# VCU_itr2.net
KiCad netlist of a schematic drawn in EAGLE
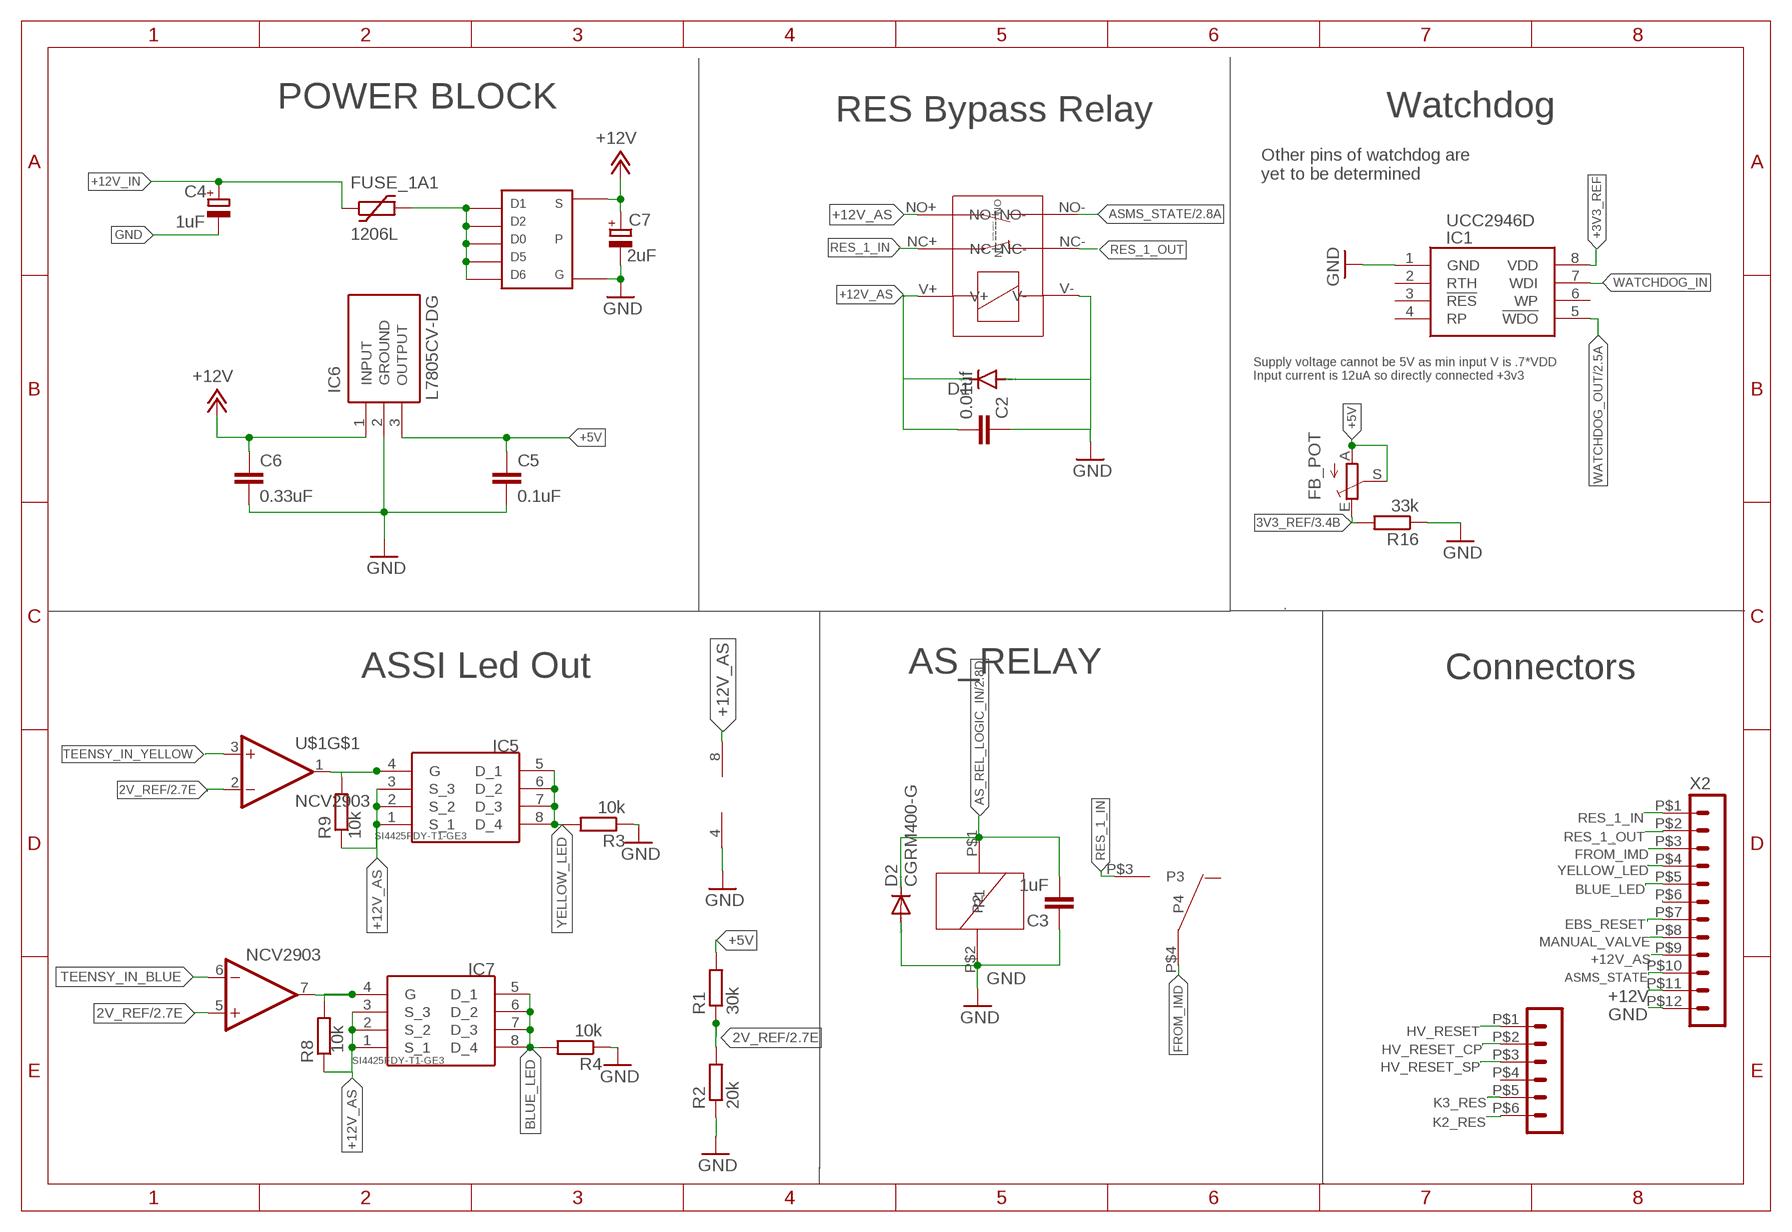
[diagram p0: schematic, sheet 1]
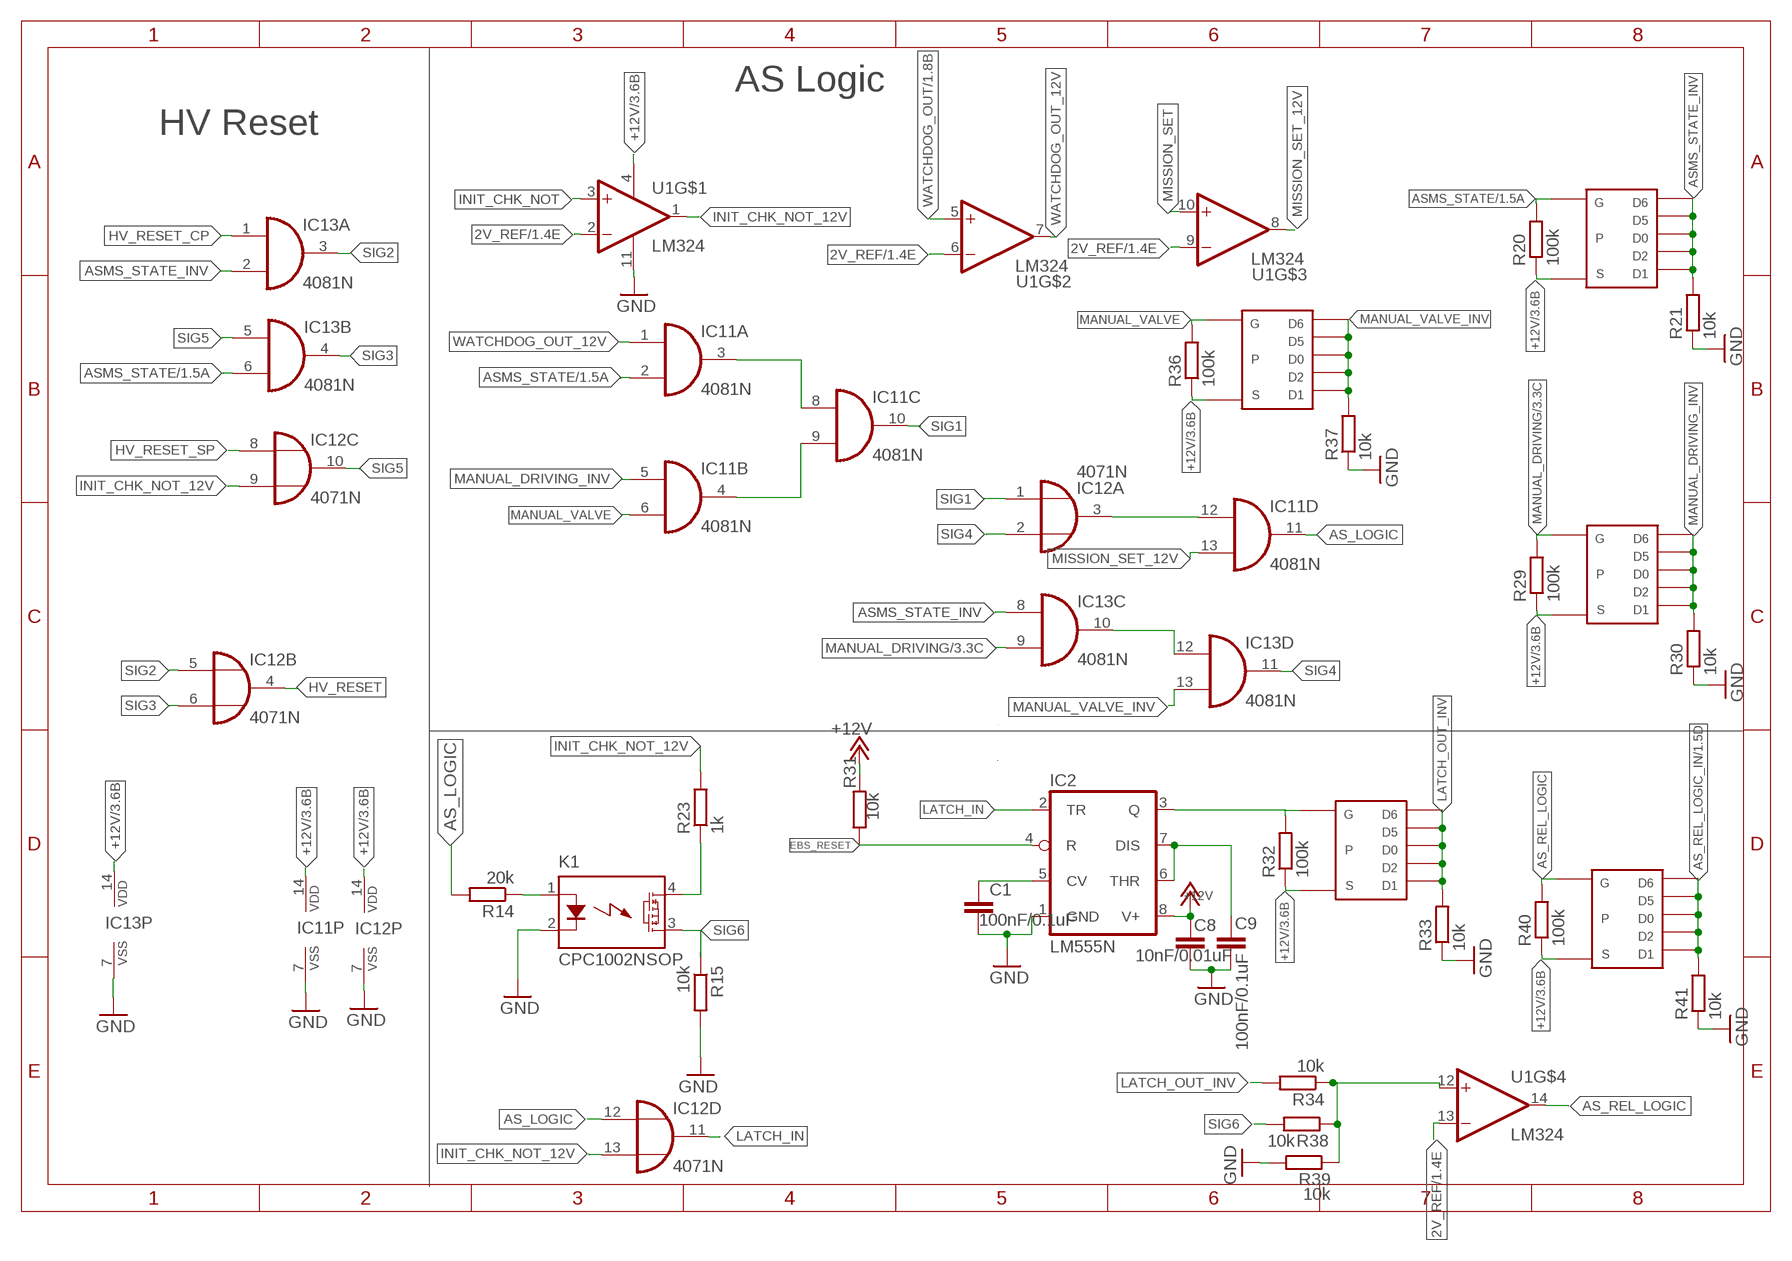
[diagram p1: schematic, sheet 2]
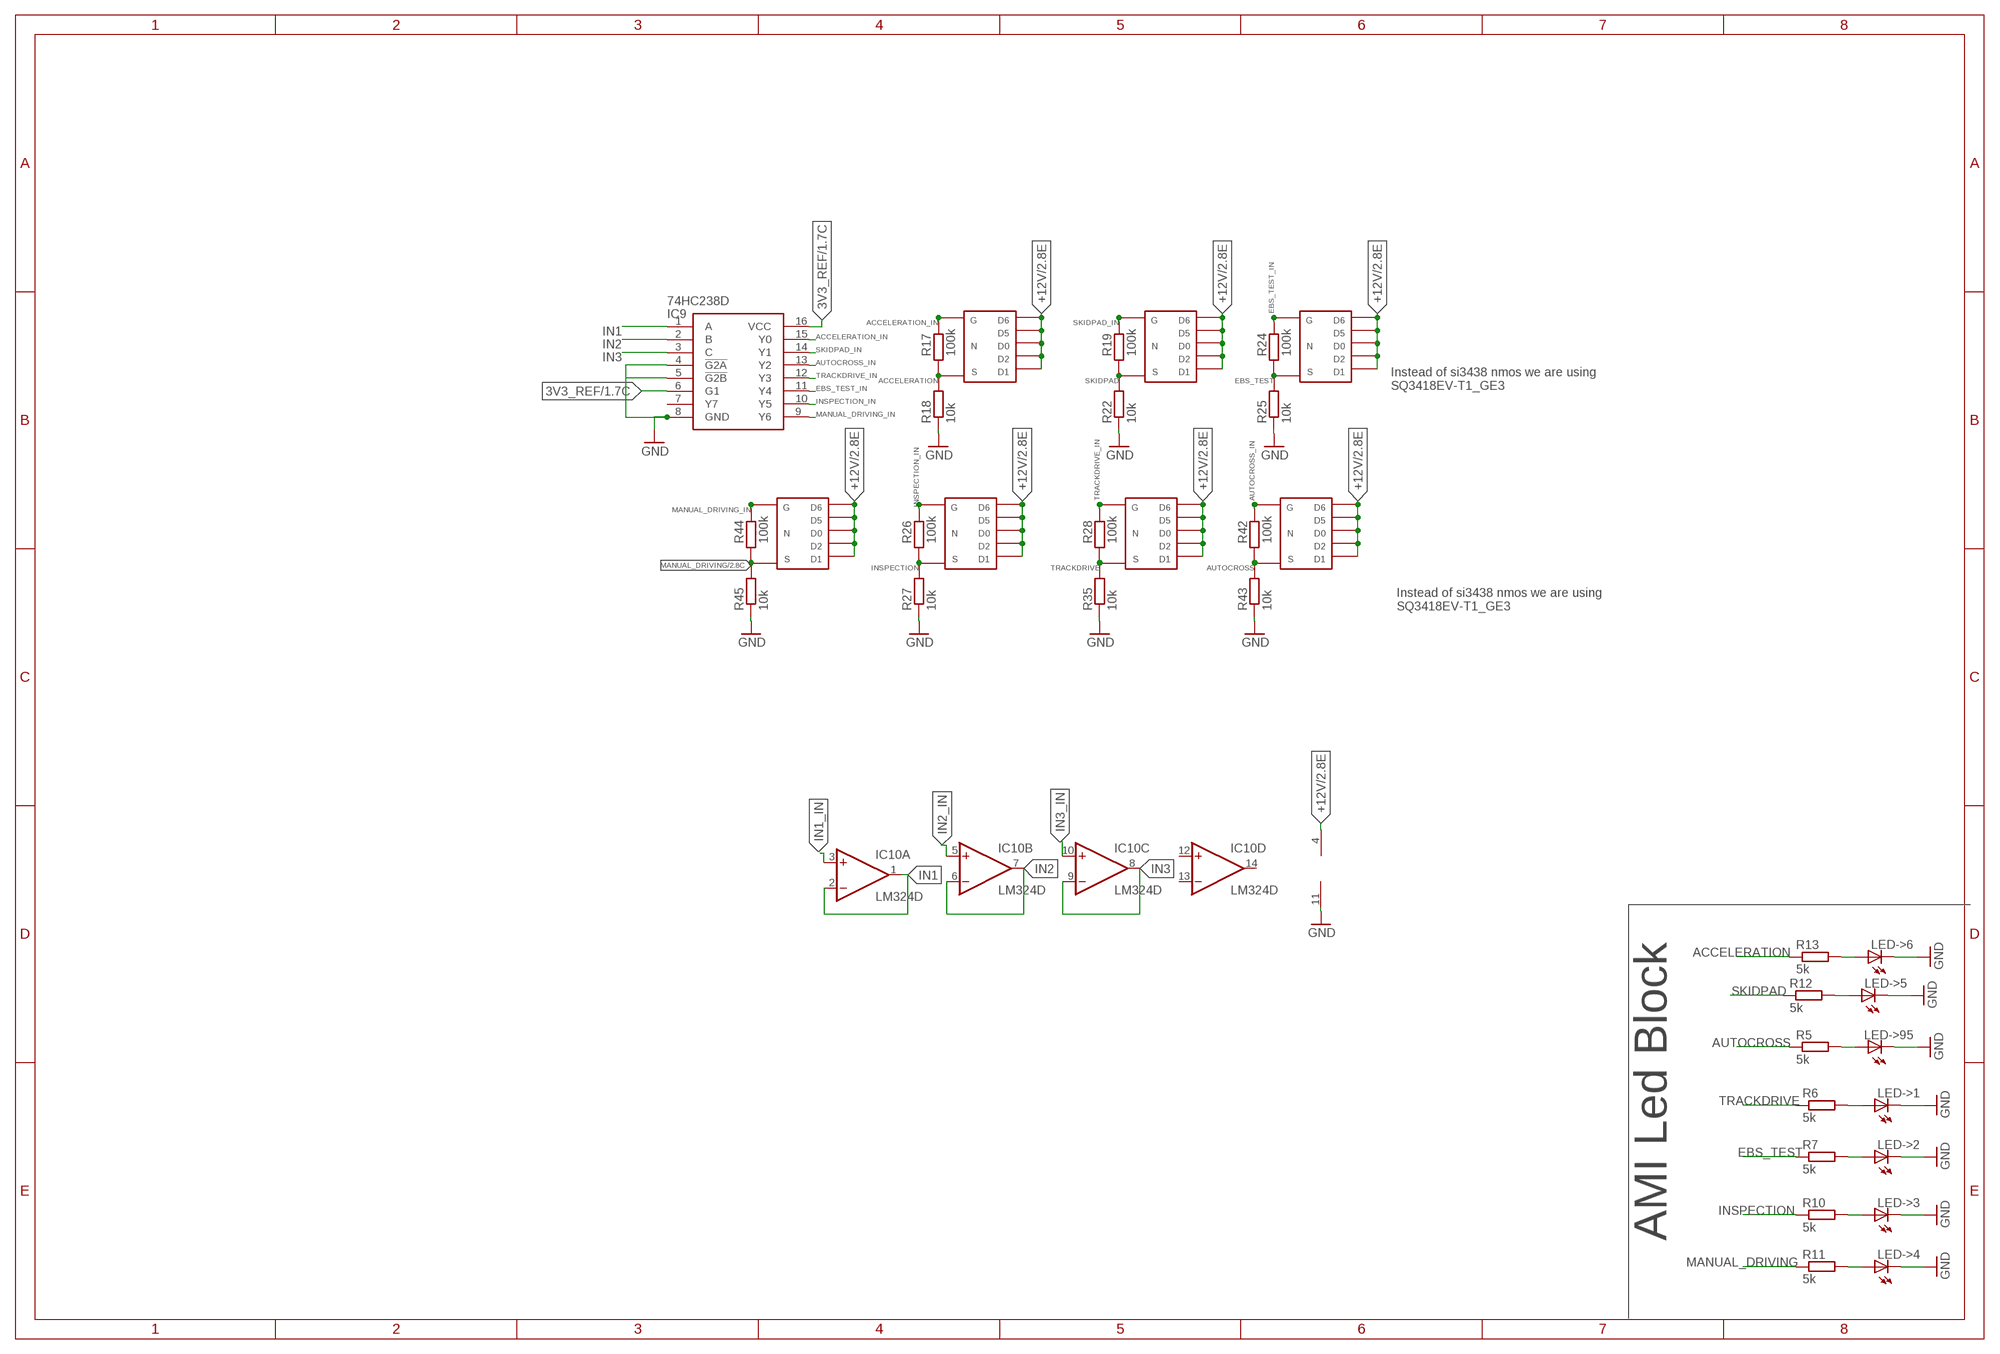
[diagram p2: schematic, sheet 3]

(export (version "E")
  (design (tool "Eeschema 10.0.6"))
  (components
    (comp (ref "BMS-CONN7")
      (value "HEADER_POS6_43045-0612")
      (footprint "eagle-import:43045-0612")
      (libsource (lib "eagle-import") (part "HEADER_POS6_?43045-0612"))
    )
    (comp (ref "C2")
      (value "0.01uf")
      (footprint "eagle-import:C1210")
      (libsource (lib "eagle-import") (part "C-EUC1210"))
    )
    (comp (ref "C3")
      (value "1uF")
      (footprint "eagle-import:C0805")
      (libsource (lib "eagle-import") (part "C-EUC0805"))
    )
    (comp (ref "C4")
      (value "1uF")
      (footprint "eagle-import:SMC_A")
      (libsource (lib "eagle-import") (part "CPOL-EUSMCA"))
    )
    (comp (ref "C5")
      (value "0.1uF")
      (footprint "eagle-import:C0805")
      (libsource (lib "eagle-import") (part "rcl_334_C-EUC0805"))
    )
    (comp (ref "C6")
      (value "0.33uF")
      (footprint "eagle-import:C0805")
      (libsource (lib "eagle-import") (part "rcl_334_C-EUC0805"))
    )
    (comp (ref "C7")
      (value "2uF")
      (footprint "eagle-import:E2,5-6")
      (libsource (lib "eagle-import") (part "CPOL-EUE2.5-6"))
    )
    (comp (ref "D1")
      (value "DIODE-DO214AC")
      (footprint "eagle-import:DO214AC")
      (libsource (lib "eagle-import") (part "DIODE-DO214AC"))
    )
    (comp (ref "D2")
      (value "CGRM400-G")
      (footprint "eagle-import:SOD-123_MINI-SMA")
      (libsource (lib "eagle-import") (part "CGRM400-G"))
    )
    (comp (ref "FB_POT")
      (value "17k")
      (footprint "eagle-import:S63S")
      (libsource (lib "eagle-import") (part "TRIM_EU-S63S"))
    )
    (comp (ref "FUSE_1A1")
      (value "1206L")
      (footprint "eagle-import:1206L")
      (libsource (lib "eagle-import") (part "1206L"))
    )
    (comp (ref "IC1")
      (value "UCC2946D")
      (footprint "eagle-import:SOIC127P600X175-8N")
      (fields (field (name "MOUSER_PART_NUMBER") "595-UCC2946D"))
      (libsource (lib "eagle-import") (part "UCC2946D"))
    )
    (comp (ref "IC5")
      (value "SI4425FDY-T1-GE3")
      (footprint "eagle-import:SOIC127P600X175-8N")
      (fields (field (name "MOUSER_PART_NUMBER") "78-SI4425FDY-T1-GE3"))
      (libsource (lib "eagle-import") (part "SI4425FDY-T1-GE3"))
    )
    (comp (ref "IC6")
      (value "L7805CV-DG")
      (footprint "eagle-import:TO255P460X1020X2008-3P")
      (fields (field (name "MOUSER_PART_NUMBER") "511-L7805CV-DG"))
      (libsource (lib "eagle-import") (part "L7805CV-DG"))
    )
    (comp (ref "IC7")
      (value "SI4425FDY-T1-GE3")
      (footprint "eagle-import:SOIC127P600X175-8N")
      (fields (field (name "MOUSER_PART_NUMBER") "78-SI4425FDY-T1-GE3"))
      (libsource (lib "eagle-import") (part "SI4425FDY-T1-GE3"))
    )
    (comp (ref "R1")
      (value "30k")
      (footprint "eagle-import:M0805")
      (libsource (lib "eagle-import") (part "IIT_BOMBAY_Racing2_R-EU_M0805"))
    )
    (comp (ref "R2")
      (value "20k")
      (footprint "eagle-import:M0805")
      (libsource (lib "eagle-import") (part "IIT_BOMBAY_Racing2_R-EU_M0805"))
    )
    (comp (ref "R3")
      (value "10k")
      (footprint "eagle-import:M0805")
      (libsource (lib "eagle-import") (part "IIT_BOMBAY_Racing2_R-EU_M0805"))
    )
    (comp (ref "R4")
      (value "10k")
      (footprint "eagle-import:M0805")
      (libsource (lib "eagle-import") (part "IIT_BOMBAY_Racing2_R-EU_M0805"))
    )
    (comp (ref "R8")
      (value "10k")
      (footprint "eagle-import:M0805")
      (libsource (lib "eagle-import") (part "IIT_BOMBAY_Racing2_R-EU_M0805"))
    )
    (comp (ref "R9")
      (value "10k")
      (footprint "eagle-import:M0805")
      (libsource (lib "eagle-import") (part "IIT_BOMBAY_Racing2_R-EU_M0805"))
    )
    (comp (ref "R16")
      (value "33k")
      (footprint "eagle-import:M0805")
      (libsource (lib "eagle-import") (part "IIT_BOMBAY_Racing2_R-EU_M0805"))
    )
    (comp (ref "SI1")
      (value "TSOP-6_PMOS")
      (footprint "eagle-import:TSOP-6_PMOS")
      (libsource (lib "eagle-import") (part "TSOP-6_PMOS"))
    )
    (comp (ref "U$1")
      (value "NCV2903")
      (footprint "eagle-import:SOIC-8")
      (libsource (lib "eagle-import") (part "NCV2903"))
    )
    (comp (ref "U$2")
      (value "G6DN_RELAY")
      (footprint "eagle-import:G6DN_RELAY")
      (libsource (lib "eagle-import") (part "G6DN_RELAY"))
    )
    (comp (ref "U$9")
      (value "SFM_RELAY")
      (footprint "eagle-import:SFM_RELAY")
      (libsource (lib "eagle-import") (part "SFM_RELAY"))
    )
    (comp (ref "X2")
      (value "HEADER_POS12_44914-1201")
      (footprint "eagle-import:44914-1201")
      (libsource (lib "eagle-import") (part "HEADER_POS12_?44914-1201"))
    )
    (comp (ref "IC9")
      (value "74HC238D")
      (footprint "eagle-import:SOIC127P600X175-16N")
      (fields (field (name "MOUSER_PART_NUMBER") "757-74HC238D"))
      (libsource (lib "eagle-import") (part "74HC238D"))
    )
    (comp (ref "IC10")
      (value "LM324D")
      (footprint "eagle-import:SO14")
      (libsource (lib "eagle-import") (part "LM324D"))
    )
    (comp (ref "LED->1")
      (value "LED-FKIT-1206")
      (footprint "eagle-import:FKIT-LED-1206")
      (libsource (lib "eagle-import") (part "LED-FKIT-1206"))
    )
    (comp (ref "LED->2")
      (value "LED-FKIT-1206")
      (footprint "eagle-import:FKIT-LED-1206")
      (libsource (lib "eagle-import") (part "LED-FKIT-1206"))
    )
    (comp (ref "LED->3")
      (value "LED-FKIT-1206")
      (footprint "eagle-import:FKIT-LED-1206")
      (libsource (lib "eagle-import") (part "LED-FKIT-1206"))
    )
    (comp (ref "LED->4")
      (value "LED-FKIT-1206")
      (footprint "eagle-import:FKIT-LED-1206")
      (libsource (lib "eagle-import") (part "LED-FKIT-1206"))
    )
    (comp (ref "LED->5")
      (value "LED-FKIT-1206")
      (footprint "eagle-import:FKIT-LED-1206")
      (libsource (lib "eagle-import") (part "LED-FKIT-1206"))
    )
    (comp (ref "LED->6")
      (value "LED-FKIT-1206")
      (footprint "eagle-import:FKIT-LED-1206")
      (libsource (lib "eagle-import") (part "LED-FKIT-1206"))
    )
    (comp (ref "LED->95")
      (value "LED-FKIT-1206")
      (footprint "eagle-import:FKIT-LED-1206")
      (libsource (lib "eagle-import") (part "LED-FKIT-1206"))
    )
    (comp (ref "R5")
      (value "5k")
      (footprint "eagle-import:R0805")
      (libsource (lib "eagle-import") (part "R-EU_R0805"))
    )
    (comp (ref "R6")
      (value "5k")
      (footprint "eagle-import:R0805")
      (libsource (lib "eagle-import") (part "R-EU_R0805"))
    )
    (comp (ref "R7")
      (value "5k")
      (footprint "eagle-import:R0805")
      (libsource (lib "eagle-import") (part "R-EU_R0805"))
    )
    (comp (ref "R10")
      (value "5k")
      (footprint "eagle-import:R0805")
      (libsource (lib "eagle-import") (part "R-EU_R0805"))
    )
    (comp (ref "R11")
      (value "5k")
      (footprint "eagle-import:R0805")
      (libsource (lib "eagle-import") (part "R-EU_R0805"))
    )
    (comp (ref "R12")
      (value "5k")
      (footprint "eagle-import:R0805")
      (libsource (lib "eagle-import") (part "R-EU_R0805"))
    )
    (comp (ref "R13")
      (value "5k")
      (footprint "eagle-import:R0805")
      (libsource (lib "eagle-import") (part "R-EU_R0805"))
    )
    (comp (ref "R17")
      (value "100k")
      (footprint "eagle-import:R0805")
      (libsource (lib "eagle-import") (part "R-EU_R0805"))
    )
    (comp (ref "R18")
      (value "10k")
      (footprint "eagle-import:M0805")
      (libsource (lib "eagle-import") (part "IIT_BOMBAY_Racing2_R-EU_M0805"))
    )
    (comp (ref "R19")
      (value "100k")
      (footprint "eagle-import:R0805")
      (libsource (lib "eagle-import") (part "R-EU_R0805"))
    )
    (comp (ref "R22")
      (value "10k")
      (footprint "eagle-import:M0805")
      (libsource (lib "eagle-import") (part "IIT_BOMBAY_Racing2_R-EU_M0805"))
    )
    (comp (ref "R24")
      (value "100k")
      (footprint "eagle-import:R0805")
      (libsource (lib "eagle-import") (part "R-EU_R0805"))
    )
    (comp (ref "R25")
      (value "10k")
      (footprint "eagle-import:M0805")
      (libsource (lib "eagle-import") (part "IIT_BOMBAY_Racing2_R-EU_M0805"))
    )
    (comp (ref "R26")
      (value "100k")
      (footprint "eagle-import:R0805")
      (libsource (lib "eagle-import") (part "R-EU_R0805"))
    )
    (comp (ref "R27")
      (value "10k")
      (footprint "eagle-import:M0805")
      (libsource (lib "eagle-import") (part "IIT_BOMBAY_Racing2_R-EU_M0805"))
    )
    (comp (ref "R28")
      (value "100k")
      (footprint "eagle-import:R0805")
      (libsource (lib "eagle-import") (part "R-EU_R0805"))
    )
    (comp (ref "R35")
      (value "10k")
      (footprint "eagle-import:M0805")
      (libsource (lib "eagle-import") (part "IIT_BOMBAY_Racing2_R-EU_M0805"))
    )
    (comp (ref "R42")
      (value "100k")
      (footprint "eagle-import:R0805")
      (libsource (lib "eagle-import") (part "R-EU_R0805"))
    )
    (comp (ref "R43")
      (value "10k")
      (footprint "eagle-import:M0805")
      (libsource (lib "eagle-import") (part "IIT_BOMBAY_Racing2_R-EU_M0805"))
    )
    (comp (ref "R44")
      (value "100k")
      (footprint "eagle-import:R0805")
      (libsource (lib "eagle-import") (part "R-EU_R0805"))
    )
    (comp (ref "R45")
      (value "10k")
      (footprint "eagle-import:M0805")
      (libsource (lib "eagle-import") (part "IIT_BOMBAY_Racing2_R-EU_M0805"))
    )
    (comp (ref "U$13")
      (value "TSOP-6_NMOS")
      (footprint "eagle-import:TSOP-6_NMOS")
      (libsource (lib "eagle-import") (part "TSOP-6_NMOS"))
    )
    (comp (ref "U$14")
      (value "TSOP-6_NMOS")
      (footprint "eagle-import:TSOP-6_NMOS")
      (libsource (lib "eagle-import") (part "TSOP-6_NMOS"))
    )
    (comp (ref "U$15")
      (value "TSOP-6_NMOS")
      (footprint "eagle-import:TSOP-6_NMOS")
      (libsource (lib "eagle-import") (part "TSOP-6_NMOS"))
    )
    (comp (ref "U$16")
      (value "TSOP-6_NMOS")
      (footprint "eagle-import:TSOP-6_NMOS")
      (libsource (lib "eagle-import") (part "TSOP-6_NMOS"))
    )
    (comp (ref "U$17")
      (value "TSOP-6_NMOS")
      (footprint "eagle-import:TSOP-6_NMOS")
      (libsource (lib "eagle-import") (part "TSOP-6_NMOS"))
    )
    (comp (ref "U$18")
      (value "TSOP-6_NMOS")
      (footprint "eagle-import:TSOP-6_NMOS")
      (libsource (lib "eagle-import") (part "TSOP-6_NMOS"))
    )
    (comp (ref "U$19")
      (value "TSOP-6_NMOS")
      (footprint "eagle-import:TSOP-6_NMOS")
      (libsource (lib "eagle-import") (part "TSOP-6_NMOS"))
    )
    (comp (ref "C1")
      (value "100nF/0.1uF")
      (footprint "eagle-import:C0805")
      (libsource (lib "eagle-import") (part "C-EUC0805"))
    )
    (comp (ref "C8")
      (value "10nF/0.01uF")
      (footprint "eagle-import:C0805")
      (libsource (lib "eagle-import") (part "C-EUC0805"))
    )
    (comp (ref "C9")
      (value "100nF/0.1uF")
      (footprint "eagle-import:C0805")
      (libsource (lib "eagle-import") (part "C-EUC0805"))
    )
    (comp (ref "IC2")
      (value "LM555N")
      (footprint "eagle-import:DIL08")
      (libsource (lib "eagle-import") (part "555NLM"))
    )
    (comp (ref "IC11")
      (value "4081N")
      (footprint "eagle-import:DIL14")
      (libsource (lib "eagle-import") (part "4081N"))
    )
    (comp (ref "IC12")
      (value "4071N")
      (footprint "eagle-import:DIL14")
      (libsource (lib "eagle-import") (part "4071N"))
    )
    (comp (ref "IC13")
      (value "4081N")
      (footprint "eagle-import:DIL14")
      (libsource (lib "eagle-import") (part "4081N"))
    )
    (comp (ref "K1")
      (value "CPC1002NSOP")
      (footprint "eagle-import:SOP04")
      (libsource (lib "eagle-import") (part "CPC1002NSOP"))
    )
    (comp (ref "R14")
      (value "20k")
      (footprint "eagle-import:R0805")
      (libsource (lib "eagle-import") (part "R-EU_R0805"))
    )
    (comp (ref "R15")
      (value "10k")
      (footprint "eagle-import:R0805")
      (libsource (lib "eagle-import") (part "R-EU_R0805"))
    )
    (comp (ref "R20")
      (value "100k")
      (footprint "eagle-import:M0805")
      (libsource (lib "eagle-import") (part "IIT_BOMBAY_Racing2_R-EU_M0805"))
    )
    (comp (ref "R21")
      (value "10k")
      (footprint "eagle-import:M0805")
      (libsource (lib "eagle-import") (part "IIT_BOMBAY_Racing2_R-EU_M0805"))
    )
    (comp (ref "R23")
      (value "1k")
      (footprint "eagle-import:M0805")
      (libsource (lib "eagle-import") (part "R-EU_M0805"))
    )
    (comp (ref "R29")
      (value "100k")
      (footprint "eagle-import:M0805")
      (libsource (lib "eagle-import") (part "IIT_BOMBAY_Racing2_R-EU_M0805"))
    )
    (comp (ref "R30")
      (value "10k")
      (footprint "eagle-import:M0805")
      (libsource (lib "eagle-import") (part "IIT_BOMBAY_Racing2_R-EU_M0805"))
    )
    (comp (ref "R31")
      (value "10k")
      (footprint "eagle-import:R0805")
      (libsource (lib "eagle-import") (part "R-EU_R0805"))
    )
    (comp (ref "R32")
      (value "100k")
      (footprint "eagle-import:M0805")
      (libsource (lib "eagle-import") (part "IIT_BOMBAY_Racing2_R-EU_M0805"))
    )
    (comp (ref "R33")
      (value "10k")
      (footprint "eagle-import:M0805")
      (libsource (lib "eagle-import") (part "IIT_BOMBAY_Racing2_R-EU_M0805"))
    )
    (comp (ref "R34")
      (value "10k")
      (footprint "eagle-import:M0805")
      (libsource (lib "eagle-import") (part "IIT_BOMBAY_Racing2_R-EU_M0805"))
    )
    (comp (ref "R36")
      (value "100k")
      (footprint "eagle-import:M0805")
      (libsource (lib "eagle-import") (part "IIT_BOMBAY_Racing2_R-EU_M0805"))
    )
    (comp (ref "R37")
      (value "10k")
      (footprint "eagle-import:M0805")
      (libsource (lib "eagle-import") (part "IIT_BOMBAY_Racing2_R-EU_M0805"))
    )
    (comp (ref "R38")
      (value "10k")
      (footprint "eagle-import:M0805")
      (libsource (lib "eagle-import") (part "IIT_BOMBAY_Racing2_R-EU_M0805"))
    )
    (comp (ref "R39")
      (value "10k")
      (footprint "eagle-import:M0805")
      (libsource (lib "eagle-import") (part "IIT_BOMBAY_Racing2_R-EU_M0805"))
    )
    (comp (ref "R40")
      (value "100k")
      (footprint "eagle-import:M0805")
      (libsource (lib "eagle-import") (part "IIT_BOMBAY_Racing2_R-EU_M0805"))
    )
    (comp (ref "R41")
      (value "10k")
      (footprint "eagle-import:M0805")
      (libsource (lib "eagle-import") (part "IIT_BOMBAY_Racing2_R-EU_M0805"))
    )
    (comp (ref "SI2")
      (value "TSOP-6_PMOS")
      (footprint "eagle-import:TSOP-6_PMOS")
      (libsource (lib "eagle-import") (part "TSOP-6_PMOS"))
    )
    (comp (ref "SI3")
      (value "TSOP-6_PMOS")
      (footprint "eagle-import:TSOP-6_PMOS")
      (libsource (lib "eagle-import") (part "TSOP-6_PMOS"))
    )
    (comp (ref "SI5")
      (value "TSOP-6_PMOS")
      (footprint "eagle-import:TSOP-6_PMOS")
      (libsource (lib "eagle-import") (part "TSOP-6_PMOS"))
    )
    (comp (ref "SI6")
      (value "TSOP-6_PMOS")
      (footprint "eagle-import:TSOP-6_PMOS")
      (libsource (lib "eagle-import") (part "TSOP-6_PMOS"))
    )
    (comp (ref "SI7")
      (value "TSOP-6_PMOS")
      (footprint "eagle-import:TSOP-6_PMOS")
      (libsource (lib "eagle-import") (part "TSOP-6_PMOS"))
    )
    (comp (ref "U1")
      (value "LM324")
      (footprint "eagle-import:SOIC127P600X175-14N")
      (description "Quad OpAmp")
      (fields (field (name "MF") "Intersil") (field (name "MP") "LM324.."))
      (libsource (lib "eagle-import") (part "LM324"))
    )
  )
  (nets
    (net (code "1") (name "+3V3_REF") (class "Default")
      (node (ref "IC1") (pin "8") (pinfunction "VDD_8") (pintype "bidirectional"))
    )
    (net (code "2") (name "+5V") (class "Default")
      (node (ref "C5") (pin "1") (pinfunction "1_1") (pintype "passive"))
      (node (ref "FB_POT") (pin "A") (pinfunction "A_A") (pintype "passive"))
      (node (ref "FB_POT") (pin "S") (pinfunction "S_S") (pintype "passive"))
      (node (ref "IC6") (pin "3") (pinfunction "OUTPUT_3") (pintype "bidirectional"))
      (node (ref "R1") (pin "2") (pinfunction "2_2") (pintype "passive"))
    )
    (net (code "3") (name "+12V") (class "Default")
      (node (ref "C6") (pin "1") (pinfunction "1_1") (pintype "passive"))
      (node (ref "C7") (pin "+") (pinfunction "+_+") (pintype "passive"))
      (node (ref "C8") (pin "1") (pinfunction "1_1") (pintype "passive"))
      (node (ref "IC11") (pin "14") (pinfunction "VDD_14") (pintype "power_in"))
      (node (ref "IC12") (pin "14") (pinfunction "VDD_14") (pintype "power_in"))
      (node (ref "IC13") (pin "14") (pinfunction "VDD_14") (pintype "power_in"))
      (node (ref "IC2") (pin "8") (pinfunction "V+_8") (pintype "power_in"))
      (node (ref "IC6") (pin "1") (pinfunction "INPUT_1") (pintype "bidirectional"))
      (node (ref "R20") (pin "1") (pinfunction "1_1") (pintype "passive"))
      (node (ref "R29") (pin "1") (pinfunction "1_1") (pintype "passive"))
      (node (ref "R31") (pin "2") (pinfunction "2_2") (pintype "passive"))
      (node (ref "R32") (pin "1") (pinfunction "1_1") (pintype "passive"))
      (node (ref "R36") (pin "1") (pinfunction "1_1") (pintype "passive"))
      (node (ref "R40") (pin "1") (pinfunction "1_1") (pintype "passive"))
      (node (ref "SI1") (pin "S") (pinfunction "S_S") (pintype "bidirectional"))
      (node (ref "SI2") (pin "S") (pinfunction "S_S") (pintype "bidirectional"))
      (node (ref "SI3") (pin "S") (pinfunction "S_S") (pintype "bidirectional"))
      (node (ref "SI5") (pin "S") (pinfunction "S_S") (pintype "bidirectional"))
      (node (ref "SI6") (pin "S") (pinfunction "S_S") (pintype "bidirectional"))
      (node (ref "SI7") (pin "S") (pinfunction "S_S") (pintype "bidirectional"))
      (node (ref "U$13") (pin "1") (pinfunction "1_1") (pintype "bidirectional"))
      (node (ref "U$13") (pin "2") (pinfunction "2_2") (pintype "bidirectional"))
      (node (ref "U$13") (pin "5") (pinfunction "5_5") (pintype "bidirectional"))
      (node (ref "U$13") (pin "6") (pinfunction "6_6") (pintype "bidirectional"))
      (node (ref "U$13") (pin "D") (pinfunction "D0_D") (pintype "bidirectional"))
      (node (ref "U$14") (pin "1") (pinfunction "1_1") (pintype "bidirectional"))
      (node (ref "U$14") (pin "2") (pinfunction "2_2") (pintype "bidirectional"))
      (node (ref "U$14") (pin "5") (pinfunction "5_5") (pintype "bidirectional"))
      (node (ref "U$14") (pin "6") (pinfunction "6_6") (pintype "bidirectional"))
      (node (ref "U$14") (pin "D") (pinfunction "D0_D") (pintype "bidirectional"))
      (node (ref "U$15") (pin "1") (pinfunction "1_1") (pintype "bidirectional"))
      (node (ref "U$15") (pin "2") (pinfunction "2_2") (pintype "bidirectional"))
      (node (ref "U$15") (pin "5") (pinfunction "5_5") (pintype "bidirectional"))
      (node (ref "U$15") (pin "6") (pinfunction "6_6") (pintype "bidirectional"))
      (node (ref "U$15") (pin "D") (pinfunction "D0_D") (pintype "bidirectional"))
      (node (ref "U$16") (pin "1") (pinfunction "1_1") (pintype "bidirectional"))
      (node (ref "U$16") (pin "2") (pinfunction "2_2") (pintype "bidirectional"))
      (node (ref "U$16") (pin "5") (pinfunction "5_5") (pintype "bidirectional"))
      (node (ref "U$16") (pin "6") (pinfunction "6_6") (pintype "bidirectional"))
      (node (ref "U$16") (pin "D") (pinfunction "D0_D") (pintype "bidirectional"))
      (node (ref "U$17") (pin "1") (pinfunction "1_1") (pintype "bidirectional"))
      (node (ref "U$17") (pin "2") (pinfunction "2_2") (pintype "bidirectional"))
      (node (ref "U$17") (pin "5") (pinfunction "5_5") (pintype "bidirectional"))
      (node (ref "U$17") (pin "6") (pinfunction "6_6") (pintype "bidirectional"))
      (node (ref "U$17") (pin "D") (pinfunction "D0_D") (pintype "bidirectional"))
      (node (ref "U$18") (pin "1") (pinfunction "1_1") (pintype "bidirectional"))
      (node (ref "U$18") (pin "2") (pinfunction "2_2") (pintype "bidirectional"))
      (node (ref "U$18") (pin "5") (pinfunction "5_5") (pintype "bidirectional"))
      (node (ref "U$18") (pin "6") (pinfunction "6_6") (pintype "bidirectional"))
      (node (ref "U$18") (pin "D") (pinfunction "D0_D") (pintype "bidirectional"))
      (node (ref "U$19") (pin "1") (pinfunction "1_1") (pintype "bidirectional"))
      (node (ref "U$19") (pin "2") (pinfunction "2_2") (pintype "bidirectional"))
      (node (ref "U$19") (pin "5") (pinfunction "5_5") (pintype "bidirectional"))
      (node (ref "U$19") (pin "6") (pinfunction "6_6") (pintype "bidirectional"))
      (node (ref "U$19") (pin "D") (pinfunction "D0_D") (pintype "bidirectional"))
      (node (ref "U1") (pin "4") (pinfunction "VCC+_4") (pintype "power_in"))
      (node (ref "X2") (pin "P$11") (pinfunction "11_P$11") (pintype "passive"))
    )
    (net (code "4") (name "+12V_AS") (class "Default")
      (node (ref "C2") (pin "2") (pinfunction "2_2") (pintype "passive"))
      (node (ref "D1") (pin "C") (pinfunction "C_C") (pintype "passive"))
      (node (ref "IC5") (pin "1") (pinfunction "S_1_1") (pintype "bidirectional"))
      (node (ref "IC5") (pin "2") (pinfunction "S_2_2") (pintype "bidirectional"))
      (node (ref "IC5") (pin "3") (pinfunction "S_3_3") (pintype "bidirectional"))
      (node (ref "IC7") (pin "1") (pinfunction "S_1_1") (pintype "bidirectional"))
      (node (ref "IC7") (pin "2") (pinfunction "S_2_2") (pintype "bidirectional"))
      (node (ref "IC7") (pin "3") (pinfunction "S_3_3") (pintype "bidirectional"))
      (node (ref "R8") (pin "1") (pinfunction "1_1") (pintype "passive"))
      (node (ref "R9") (pin "1") (pinfunction "1_1") (pintype "passive"))
      (node (ref "U$1") (pin "8") (pinfunction "V+_8") (pintype "power_in"))
      (node (ref "U$9") (pin "NO+") (pinfunction "NO+_NO+") (pintype "bidirectional"))
      (node (ref "U$9") (pin "V+") (pinfunction "V+_V+") (pintype "bidirectional"))
      (node (ref "X2") (pin "P$9") (pinfunction "9_P$9") (pintype "passive"))
    )
    (net (code "5") (name "+12V_IN") (class "Default")
      (node (ref "C4") (pin "+") (pinfunction "+_+") (pintype "passive"))
      (node (ref "FUSE_1A1") (pin "P$1") (pinfunction "1_P$1") (pintype "passive"))
    )
    (net (code "6") (name "2V_REF") (class "Default")
      (node (ref "R1") (pin "1") (pinfunction "1_1") (pintype "passive"))
      (node (ref "R2") (pin "2") (pinfunction "2_2") (pintype "passive"))
      (node (ref "U$1") (pin "2") (pinfunction "-IN_2") (pintype "input"))
      (node (ref "U$1") (pin "5") (pinfunction "+IN_5") (pintype "input"))
      (node (ref "U1") (pin "13") (pinfunction "INVERTING_INPUT4_13") (pintype "input"))
      (node (ref "U1") (pin "2") (pinfunction "INVERTING_INPUT1_2") (pintype "input"))
      (node (ref "U1") (pin "6") (pinfunction "INVERTING_INPUT2_6") (pintype "input"))
      (node (ref "U1") (pin "9") (pinfunction "INVERTING_INPUT3_9") (pintype "input"))
    )
    (net (code "7") (name "3V3_REF") (class "Default")
      (node (ref "FB_POT") (pin "E") (pinfunction "E_E") (pintype "passive"))
      (node (ref "IC9") (pin "16") (pinfunction "VCC_16") (pintype "bidirectional"))
      (node (ref "IC9") (pin "6") (pinfunction "G1_6") (pintype "bidirectional"))
      (node (ref "R16") (pin "2") (pinfunction "2_2") (pintype "passive"))
    )
    (net (code "8") (name "ACCELERATION") (class "Default")
      (node (ref "R13") (pin "1") (pinfunction "1_1") (pintype "passive"))
      (node (ref "R17") (pin "1") (pinfunction "1_1") (pintype "passive"))
      (node (ref "R18") (pin "2") (pinfunction "2_2") (pintype "passive"))
      (node (ref "U$13") (pin "S") (pinfunction "S_S") (pintype "bidirectional"))
    )
    (net (code "9") (name "ACCELERATION_IN") (class "Default")
      (node (ref "IC9") (pin "15") (pinfunction "Y0_15") (pintype "bidirectional"))
      (node (ref "R17") (pin "2") (pinfunction "2_2") (pintype "passive"))
      (node (ref "U$13") (pin "G") (pinfunction "G_G") (pintype "bidirectional"))
    )
    (net (code "10") (name "ASMS_STATE") (class "Default")
      (node (ref "IC11") (pin "2") (pinfunction "I1_2") (pintype "input"))
      (node (ref "IC13") (pin "6") (pinfunction "I1_6") (pintype "input"))
      (node (ref "R20") (pin "2") (pinfunction "2_2") (pintype "passive"))
      (node (ref "SI5") (pin "G") (pinfunction "G_G") (pintype "bidirectional"))
      (node (ref "U$9") (pin "NO-") (pinfunction "NO-_NO-") (pintype "bidirectional"))
      (node (ref "X2") (pin "P$10") (pinfunction "10_P$10") (pintype "passive"))
    )
    (net (code "11") (name "ASMS_STATE_INV") (class "Default")
      (node (ref "IC13") (pin "2") (pinfunction "I1_2") (pintype "input"))
      (node (ref "IC13") (pin "8") (pinfunction "I0_8") (pintype "input"))
      (node (ref "R21") (pin "2") (pinfunction "2_2") (pintype "passive"))
      (node (ref "SI5") (pin "1") (pinfunction "1_1") (pintype "bidirectional"))
      (node (ref "SI5") (pin "2") (pinfunction "2_2") (pintype "bidirectional"))
      (node (ref "SI5") (pin "5") (pinfunction "5_5") (pintype "bidirectional"))
      (node (ref "SI5") (pin "6") (pinfunction "6_6") (pintype "bidirectional"))
      (node (ref "SI5") (pin "D") (pinfunction "D0_D") (pintype "bidirectional"))
    )
    (net (code "12") (name "AS_LOGIC") (class "Default")
      (node (ref "IC11") (pin "11") (pinfunction "O_11") (pintype "output"))
      (node (ref "IC12") (pin "12") (pinfunction "I0_12") (pintype "input"))
      (node (ref "R14") (pin "2") (pinfunction "2_2") (pintype "passive"))
    )
    (net (code "13") (name "AS_REL_LOGIC") (class "Default")
      (node (ref "R40") (pin "2") (pinfunction "2_2") (pintype "passive"))
      (node (ref "SI3") (pin "G") (pinfunction "G_G") (pintype "bidirectional"))
      (node (ref "U1") (pin "14") (pinfunction "OUTPUT4_14") (pintype "output"))
    )
    (net (code "14") (name "AS_REL_LOGIC_IN") (class "Default")
      (node (ref "C3") (pin "2") (pinfunction "2_2") (pintype "passive"))
      (node (ref "D2") (pin "C") (pinfunction "C_C") (pintype "passive"))
      (node (ref "R41") (pin "2") (pinfunction "2_2") (pintype "passive"))
      (node (ref "SI3") (pin "1") (pinfunction "1_1") (pintype "bidirectional"))
      (node (ref "SI3") (pin "2") (pinfunction "2_2") (pintype "bidirectional"))
      (node (ref "SI3") (pin "5") (pinfunction "5_5") (pintype "bidirectional"))
      (node (ref "SI3") (pin "6") (pinfunction "6_6") (pintype "bidirectional"))
      (node (ref "SI3") (pin "D") (pinfunction "D0_D") (pintype "bidirectional"))
      (node (ref "U$2") (pin "P$1") (pinfunction "P1_P$1") (pintype "bidirectional"))
    )
    (net (code "15") (name "AUTOCROSS") (class "Default")
      (node (ref "R42") (pin "1") (pinfunction "1_1") (pintype "passive"))
      (node (ref "R43") (pin "2") (pinfunction "2_2") (pintype "passive"))
      (node (ref "R5") (pin "1") (pinfunction "1_1") (pintype "passive"))
      (node (ref "U$18") (pin "S") (pinfunction "S_S") (pintype "bidirectional"))
    )
    (net (code "16") (name "AUTOCROSS_IN") (class "Default")
      (node (ref "IC9") (pin "13") (pinfunction "Y2_13") (pintype "bidirectional"))
      (node (ref "R42") (pin "2") (pinfunction "2_2") (pintype "passive"))
      (node (ref "U$18") (pin "G") (pinfunction "G_G") (pintype "bidirectional"))
    )
    (net (code "17") (name "BLUE_LED") (class "Default")
      (node (ref "IC7") (pin "5") (pinfunction "D_1_5") (pintype "bidirectional"))
      (node (ref "IC7") (pin "6") (pinfunction "D_2_6") (pintype "bidirectional"))
      (node (ref "IC7") (pin "7") (pinfunction "D_3_7") (pintype "bidirectional"))
      (node (ref "IC7") (pin "8") (pinfunction "D_4_8") (pintype "bidirectional"))
      (node (ref "R4") (pin "2") (pinfunction "2_2") (pintype "passive"))
      (node (ref "X2") (pin "P$5") (pinfunction "5_P$5") (pintype "passive"))
    )
    (net (code "18") (name "EBS_RESET") (class "Default")
      (node (ref "IC2") (pin "4") (pinfunction "R_4") (pintype "input"))
      (node (ref "R31") (pin "1") (pinfunction "1_1") (pintype "passive"))
      (node (ref "X2") (pin "P$7") (pinfunction "7_P$7") (pintype "passive"))
    )
    (net (code "19") (name "EBS_TEST") (class "Default")
      (node (ref "R24") (pin "1") (pinfunction "1_1") (pintype "passive"))
      (node (ref "R25") (pin "2") (pinfunction "2_2") (pintype "passive"))
      (node (ref "R7") (pin "1") (pinfunction "1_1") (pintype "passive"))
      (node (ref "U$15") (pin "S") (pinfunction "S_S") (pintype "bidirectional"))
    )
    (net (code "20") (name "EBS_TEST_IN") (class "Default")
      (node (ref "IC9") (pin "11") (pinfunction "Y4_11") (pintype "bidirectional"))
      (node (ref "R24") (pin "2") (pinfunction "2_2") (pintype "passive"))
      (node (ref "U$15") (pin "G") (pinfunction "G_G") (pintype "bidirectional"))
    )
    (net (code "21") (name "FROM_IMD") (class "Default")
      (node (ref "U$2") (pin "P$4") (pinfunction "P4_P$4") (pintype "bidirectional"))
      (node (ref "X2") (pin "P$3") (pinfunction "3_P$3") (pintype "passive"))
    )
    (net (code "22") (name "GND") (class "Default")
      (node (ref "C1") (pin "2") (pinfunction "2_2") (pintype "passive"))
      (node (ref "C2") (pin "1") (pinfunction "1_1") (pintype "passive"))
      (node (ref "C3") (pin "1") (pinfunction "1_1") (pintype "passive"))
      (node (ref "C4") (pin "-") (pinfunction "-_-") (pintype "passive"))
      (node (ref "C5") (pin "2") (pinfunction "2_2") (pintype "passive"))
      (node (ref "C6") (pin "2") (pinfunction "2_2") (pintype "passive"))
      (node (ref "C7") (pin "-") (pinfunction "-_-") (pintype "passive"))
      (node (ref "C8") (pin "2") (pinfunction "2_2") (pintype "passive"))
      (node (ref "C9") (pin "2") (pinfunction "2_2") (pintype "passive"))
      (node (ref "D1") (pin "A") (pinfunction "A_A") (pintype "passive"))
      (node (ref "D2") (pin "A") (pinfunction "A_A") (pintype "passive"))
      (node (ref "IC1") (pin "1") (pinfunction "GND_1") (pintype "bidirectional"))
      (node (ref "IC10") (pin "11") (pinfunction "V-_11") (pintype "power_in"))
      (node (ref "IC11") (pin "7") (pinfunction "VSS_7") (pintype "power_in"))
      (node (ref "IC12") (pin "7") (pinfunction "VSS_7") (pintype "power_in"))
      (node (ref "IC13") (pin "7") (pinfunction "VSS_7") (pintype "power_in"))
      (node (ref "IC2") (pin "1") (pinfunction "GND_1") (pintype "power_in"))
      (node (ref "IC6") (pin "2") (pinfunction "GROUND_2") (pintype "bidirectional"))
      (node (ref "IC9") (pin "4") (pinfunction "~{G2A}_4") (pintype "bidirectional"))
      (node (ref "IC9") (pin "5") (pinfunction "~{G2B}_5") (pintype "bidirectional"))
      (node (ref "IC9") (pin "8") (pinfunction "GND_8") (pintype "bidirectional"))
      (node (ref "K1") (pin "2") (pinfunction "K_2") (pintype "passive"))
      (node (ref "LED->1") (pin "C") (pinfunction "C_C") (pintype "passive"))
      (node (ref "LED->2") (pin "C") (pinfunction "C_C") (pintype "passive"))
      (node (ref "LED->3") (pin "C") (pinfunction "C_C") (pintype "passive"))
      (node (ref "LED->4") (pin "C") (pinfunction "C_C") (pintype "passive"))
      (node (ref "LED->5") (pin "C") (pinfunction "C_C") (pintype "passive"))
      (node (ref "LED->6") (pin "C") (pinfunction "C_C") (pintype "passive"))
      (node (ref "LED->95") (pin "C") (pinfunction "C_C") (pintype "passive"))
      (node (ref "R15") (pin "2") (pinfunction "2_2") (pintype "passive"))
      (node (ref "R16") (pin "1") (pinfunction "1_1") (pintype "passive"))
      (node (ref "R18") (pin "1") (pinfunction "1_1") (pintype "passive"))
      (node (ref "R2") (pin "1") (pinfunction "1_1") (pintype "passive"))
      (node (ref "R21") (pin "1") (pinfunction "1_1") (pintype "passive"))
      (node (ref "R22") (pin "1") (pinfunction "1_1") (pintype "passive"))
      (node (ref "R25") (pin "1") (pinfunction "1_1") (pintype "passive"))
      (node (ref "R27") (pin "1") (pinfunction "1_1") (pintype "passive"))
      (node (ref "R3") (pin "1") (pinfunction "1_1") (pintype "passive"))
      (node (ref "R30") (pin "1") (pinfunction "1_1") (pintype "passive"))
      (node (ref "R33") (pin "1") (pinfunction "1_1") (pintype "passive"))
      (node (ref "R35") (pin "1") (pinfunction "1_1") (pintype "passive"))
      (node (ref "R37") (pin "1") (pinfunction "1_1") (pintype "passive"))
      (node (ref "R39") (pin "2") (pinfunction "2_2") (pintype "passive"))
      (node (ref "R4") (pin "1") (pinfunction "1_1") (pintype "passive"))
      (node (ref "R41") (pin "1") (pinfunction "1_1") (pintype "passive"))
      (node (ref "R43") (pin "1") (pinfunction "1_1") (pintype "passive"))
      (node (ref "R45") (pin "1") (pinfunction "1_1") (pintype "passive"))
      (node (ref "SI1") (pin "G") (pinfunction "G_G") (pintype "bidirectional"))
      (node (ref "U$1") (pin "4") (pinfunction "V-_4") (pintype "power_in"))
      (node (ref "U$2") (pin "P$2") (pinfunction "P2_P$2") (pintype "bidirectional"))
      (node (ref "U$9") (pin "V-") (pinfunction "V-_V-") (pintype "bidirectional"))
      (node (ref "U1") (pin "11") (pinfunction "VCC-_11") (pintype "power_in"))
      (node (ref "X2") (pin "P$12") (pinfunction "12_P$12") (pintype "passive"))
    )
    (net (code "23") (name "HV_RESET") (class "Default")
      (node (ref "BMS-CONN7") (pin "P$1") (pinfunction "1_P$1") (pintype "passive"))
      (node (ref "IC12") (pin "4") (pinfunction "O_4") (pintype "output"))
    )
    (net (code "24") (name "HV_RESET_CP") (class "Default")
      (node (ref "BMS-CONN7") (pin "P$2") (pinfunction "2_P$2") (pintype "passive"))
      (node (ref "IC13") (pin "1") (pinfunction "I0_1") (pintype "input"))
    )
    (net (code "25") (name "HV_RESET_SP") (class "Default")
      (node (ref "BMS-CONN7") (pin "P$3") (pinfunction "3_P$3") (pintype "passive"))
      (node (ref "IC12") (pin "8") (pinfunction "I0_8") (pintype "input"))
    )
    (net (code "26") (name "IN1") (class "Default")
      (node (ref "IC10") (pin "1") (pinfunction "OUT_1") (pintype "output"))
      (node (ref "IC10") (pin "2") (pinfunction "-IN_2") (pintype "input"))
      (node (ref "IC9") (pin "1") (pinfunction "A_1") (pintype "bidirectional"))
    )
    (net (code "27") (name "IN1_IN") (class "Default")
      (node (ref "IC10") (pin "3") (pinfunction "+IN_3") (pintype "input"))
    )
    (net (code "28") (name "IN2") (class "Default")
      (node (ref "IC10") (pin "6") (pinfunction "-IN_6") (pintype "input"))
      (node (ref "IC10") (pin "7") (pinfunction "OUT_7") (pintype "output"))
      (node (ref "IC9") (pin "2") (pinfunction "B_2") (pintype "bidirectional"))
    )
    (net (code "29") (name "IN2_IN") (class "Default")
      (node (ref "IC10") (pin "5") (pinfunction "+IN_5") (pintype "input"))
    )
    (net (code "30") (name "IN3") (class "Default")
      (node (ref "IC10") (pin "8") (pinfunction "OUT_8") (pintype "output"))
      (node (ref "IC10") (pin "9") (pinfunction "-IN_9") (pintype "input"))
      (node (ref "IC9") (pin "3") (pinfunction "C_3") (pintype "bidirectional"))
    )
    (net (code "31") (name "IN3_IN") (class "Default")
      (node (ref "IC10") (pin "10") (pinfunction "+IN_10") (pintype "input"))
    )
    (net (code "32") (name "INIT_CHK_NOT") (class "Default")
      (node (ref "U1") (pin "3") (pinfunction "NON-INVERTING_INPUT1_3") (pintype "input"))
    )
    (net (code "33") (name "INIT_CHK_NOT_12V") (class "Default")
      (node (ref "IC12") (pin "13") (pinfunction "I1_13") (pintype "input"))
      (node (ref "IC12") (pin "9") (pinfunction "I1_9") (pintype "input"))
      (node (ref "R23") (pin "2") (pinfunction "2_2") (pintype "passive"))
      (node (ref "U1") (pin "1") (pinfunction "OUTPUT1_1") (pintype "output"))
    )
    (net (code "34") (name "INSPECTION") (class "Default")
      (node (ref "R10") (pin "1") (pinfunction "1_1") (pintype "passive"))
      (node (ref "R26") (pin "1") (pinfunction "1_1") (pintype "passive"))
      (node (ref "R27") (pin "2") (pinfunction "2_2") (pintype "passive"))
      (node (ref "U$16") (pin "S") (pinfunction "S_S") (pintype "bidirectional"))
    )
    (net (code "35") (name "INSPECTION_IN") (class "Default")
      (node (ref "IC9") (pin "10") (pinfunction "Y5_10") (pintype "bidirectional"))
      (node (ref "R26") (pin "2") (pinfunction "2_2") (pintype "passive"))
      (node (ref "U$16") (pin "G") (pinfunction "G_G") (pintype "bidirectional"))
    )
    (net (code "36") (name "K2_RES") (class "Default")
      (node (ref "BMS-CONN7") (pin "P$6") (pinfunction "6_P$6") (pintype "passive"))
    )
    (net (code "37") (name "K3_RES") (class "Default")
      (node (ref "BMS-CONN7") (pin "P$5") (pinfunction "5_P$5") (pintype "passive"))
    )
    (net (code "38") (name "LATCH_IN") (class "Default")
      (node (ref "IC12") (pin "11") (pinfunction "O_11") (pintype "output"))
      (node (ref "IC2") (pin "2") (pinfunction "TR_2") (pintype "input"))
    )
    (net (code "39") (name "LATCH_OUT_INV") (class "Default")
      (node (ref "R33") (pin "2") (pinfunction "2_2") (pintype "passive"))
      (node (ref "R34") (pin "2") (pinfunction "2_2") (pintype "passive"))
      (node (ref "SI2") (pin "1") (pinfunction "1_1") (pintype "bidirectional"))
      (node (ref "SI2") (pin "2") (pinfunction "2_2") (pintype "bidirectional"))
      (node (ref "SI2") (pin "5") (pinfunction "5_5") (pintype "bidirectional"))
      (node (ref "SI2") (pin "6") (pinfunction "6_6") (pintype "bidirectional"))
      (node (ref "SI2") (pin "D") (pinfunction "D0_D") (pintype "bidirectional"))
    )
    (net (code "40") (name "MANUAL_DRIVING") (class "Default")
      (node (ref "IC13") (pin "9") (pinfunction "I1_9") (pintype "input"))
      (node (ref "R11") (pin "1") (pinfunction "1_1") (pintype "passive"))
      (node (ref "R29") (pin "2") (pinfunction "2_2") (pintype "passive"))
      (node (ref "R32") (pin "2") (pinfunction "2_2") (pintype "passive"))
      (node (ref "R44") (pin "1") (pinfunction "1_1") (pintype "passive"))
      (node (ref "R45") (pin "2") (pinfunction "2_2") (pintype "passive"))
      (node (ref "SI2") (pin "G") (pinfunction "G_G") (pintype "bidirectional"))
      (node (ref "SI6") (pin "G") (pinfunction "G_G") (pintype "bidirectional"))
      (node (ref "U$19") (pin "S") (pinfunction "S_S") (pintype "bidirectional"))
    )
    (net (code "41") (name "MANUAL_DRIVING_IN") (class "Default")
      (node (ref "IC9") (pin "9") (pinfunction "Y6_9") (pintype "bidirectional"))
      (node (ref "R44") (pin "2") (pinfunction "2_2") (pintype "passive"))
      (node (ref "U$19") (pin "G") (pinfunction "G_G") (pintype "bidirectional"))
    )
    (net (code "42") (name "MANUAL_DRIVING_INV") (class "Default")
      (node (ref "IC11") (pin "5") (pinfunction "I0_5") (pintype "input"))
      (node (ref "R30") (pin "2") (pinfunction "2_2") (pintype "passive"))
      (node (ref "SI6") (pin "1") (pinfunction "1_1") (pintype "bidirectional"))
      (node (ref "SI6") (pin "2") (pinfunction "2_2") (pintype "bidirectional"))
      (node (ref "SI6") (pin "5") (pinfunction "5_5") (pintype "bidirectional"))
      (node (ref "SI6") (pin "6") (pinfunction "6_6") (pintype "bidirectional"))
      (node (ref "SI6") (pin "D") (pinfunction "D0_D") (pintype "bidirectional"))
    )
    (net (code "43") (name "MANUAL_VALVE") (class "Default")
      (node (ref "IC11") (pin "6") (pinfunction "I1_6") (pintype "input"))
      (node (ref "R36") (pin "2") (pinfunction "2_2") (pintype "passive"))
      (node (ref "SI7") (pin "G") (pinfunction "G_G") (pintype "bidirectional"))
      (node (ref "X2") (pin "P$8") (pinfunction "8_P$8") (pintype "passive"))
    )
    (net (code "44") (name "MANUAL_VALVE_INV") (class "Default")
      (node (ref "IC13") (pin "13") (pinfunction "I1_13") (pintype "input"))
      (node (ref "R37") (pin "2") (pinfunction "2_2") (pintype "passive"))
      (node (ref "SI7") (pin "1") (pinfunction "1_1") (pintype "bidirectional"))
      (node (ref "SI7") (pin "2") (pinfunction "2_2") (pintype "bidirectional"))
      (node (ref "SI7") (pin "5") (pinfunction "5_5") (pintype "bidirectional"))
      (node (ref "SI7") (pin "6") (pinfunction "6_6") (pintype "bidirectional"))
      (node (ref "SI7") (pin "D") (pinfunction "D0_D") (pintype "bidirectional"))
    )
    (net (code "45") (name "MISSION_SET") (class "Default")
      (node (ref "U1") (pin "10") (pinfunction "NON-INVERTING_INPUT3_10") (pintype "input"))
    )
    (net (code "46") (name "MISSION_SET_12V") (class "Default")
      (node (ref "IC11") (pin "13") (pinfunction "I1_13") (pintype "input"))
      (node (ref "U1") (pin "8") (pinfunction "OUTPUT3_8") (pintype "output"))
    )
    (net (code "47") (name "Net-(FUSE_1A1-2)") (class "Default")
      (node (ref "FUSE_1A1") (pin "P$2") (pinfunction "2_P$2") (pintype "passive"))
      (node (ref "SI1") (pin "1") (pinfunction "1_1") (pintype "bidirectional"))
      (node (ref "SI1") (pin "2") (pinfunction "2_2") (pintype "bidirectional"))
      (node (ref "SI1") (pin "5") (pinfunction "5_5") (pintype "bidirectional"))
      (node (ref "SI1") (pin "6") (pinfunction "6_6") (pintype "bidirectional"))
      (node (ref "SI1") (pin "D") (pinfunction "D0_D") (pintype "bidirectional"))
    )
    (net (code "48") (name "Net-(IC2-CV)") (class "Default")
      (node (ref "C1") (pin "1") (pinfunction "1_1") (pintype "passive"))
      (node (ref "IC2") (pin "5") (pinfunction "CV_5") (pintype "input"))
    )
    (net (code "49") (name "Net-(IC2-DIS)") (class "Default")
      (node (ref "C9") (pin "1") (pinfunction "1_1") (pintype "passive"))
      (node (ref "IC2") (pin "6") (pinfunction "THR_6") (pintype "input"))
      (node (ref "IC2") (pin "7") (pinfunction "DIS_7") (pintype "input"))
    )
    (net (code "50") (name "Net-(IC5-G)") (class "Default")
      (node (ref "IC5") (pin "4") (pinfunction "G_4") (pintype "bidirectional"))
      (node (ref "R9") (pin "2") (pinfunction "2_2") (pintype "passive"))
      (node (ref "U$1") (pin "1") (pinfunction "OUT_1") (pintype "output"))
    )
    (net (code "51") (name "Net-(IC7-G)") (class "Default")
      (node (ref "IC7") (pin "4") (pinfunction "G_4") (pintype "bidirectional"))
      (node (ref "R8") (pin "2") (pinfunction "2_2") (pintype "passive"))
      (node (ref "U$1") (pin "7") (pinfunction "OUT_7") (pintype "output"))
    )
    (net (code "52") (name "Net-(IC11A-O)") (class "Default")
      (node (ref "IC11") (pin "3") (pinfunction "O_3") (pintype "output"))
      (node (ref "IC11") (pin "8") (pinfunction "I0_8") (pintype "input"))
    )
    (net (code "53") (name "Net-(IC11B-O)") (class "Default")
      (node (ref "IC11") (pin "4") (pinfunction "O_4") (pintype "output"))
      (node (ref "IC11") (pin "9") (pinfunction "I1_9") (pintype "input"))
    )
    (net (code "54") (name "Net-(IC11D-I0)") (class "Default")
      (node (ref "IC11") (pin "12") (pinfunction "I0_12") (pintype "input"))
      (node (ref "IC12") (pin "3") (pinfunction "O_3") (pintype "output"))
    )
    (net (code "55") (name "Net-(IC13C-O)") (class "Default")
      (node (ref "IC13") (pin "10") (pinfunction "O_10") (pintype "output"))
      (node (ref "IC13") (pin "12") (pinfunction "I0_12") (pintype "input"))
    )
    (net (code "56") (name "Net-(K1-A)") (class "Default")
      (node (ref "K1") (pin "1") (pinfunction "A_1") (pintype "passive"))
      (node (ref "R14") (pin "1") (pinfunction "1_1") (pintype "passive"))
    )
    (net (code "57") (name "Net-(K1-DS1)") (class "Default")
      (node (ref "K1") (pin "4") (pinfunction "DS1_4") (pintype "passive"))
      (node (ref "R23") (pin "1") (pinfunction "1_1") (pintype "passive"))
    )
    (net (code "58") (name "Net-(LED->1-PadA)") (class "Default")
      (node (ref "LED->1") (pin "A") (pinfunction "A_A") (pintype "passive"))
      (node (ref "R6") (pin "2") (pinfunction "2_2") (pintype "passive"))
    )
    (net (code "59") (name "Net-(LED->2-PadA)") (class "Default")
      (node (ref "LED->2") (pin "A") (pinfunction "A_A") (pintype "passive"))
      (node (ref "R7") (pin "2") (pinfunction "2_2") (pintype "passive"))
    )
    (net (code "60") (name "Net-(LED->3-PadA)") (class "Default")
      (node (ref "LED->3") (pin "A") (pinfunction "A_A") (pintype "passive"))
      (node (ref "R10") (pin "2") (pinfunction "2_2") (pintype "passive"))
    )
    (net (code "61") (name "Net-(LED->4-PadA)") (class "Default")
      (node (ref "LED->4") (pin "A") (pinfunction "A_A") (pintype "passive"))
      (node (ref "R11") (pin "2") (pinfunction "2_2") (pintype "passive"))
    )
    (net (code "62") (name "Net-(LED->5-PadA)") (class "Default")
      (node (ref "LED->5") (pin "A") (pinfunction "A_A") (pintype "passive"))
      (node (ref "R12") (pin "2") (pinfunction "2_2") (pintype "passive"))
    )
    (net (code "63") (name "Net-(LED->6-PadA)") (class "Default")
      (node (ref "LED->6") (pin "A") (pinfunction "A_A") (pintype "passive"))
      (node (ref "R13") (pin "2") (pinfunction "2_2") (pintype "passive"))
    )
    (net (code "64") (name "Net-(LED->95-PadA)") (class "Default")
      (node (ref "LED->95") (pin "A") (pinfunction "A_A") (pintype "passive"))
      (node (ref "R5") (pin "2") (pinfunction "2_2") (pintype "passive"))
    )
    (net (code "65") (name "Net-(U1D-NON-INVERTING_INPUT4)") (class "Default")
      (node (ref "R34") (pin "1") (pinfunction "1_1") (pintype "passive"))
      (node (ref "R38") (pin "1") (pinfunction "1_1") (pintype "passive"))
      (node (ref "R39") (pin "1") (pinfunction "1_1") (pintype "passive"))
      (node (ref "U1") (pin "12") (pinfunction "NON-INVERTING_INPUT4_12") (pintype "input"))
    )
    (net (code "66") (name "RES_1_IN") (class "Default")
      (node (ref "U$2") (pin "P$3") (pinfunction "P3_P$3") (pintype "bidirectional"))
      (node (ref "U$9") (pin "NC+") (pinfunction "NC+_NC+") (pintype "bidirectional"))
      (node (ref "X2") (pin "P$1") (pinfunction "1_P$1") (pintype "passive"))
    )
    (net (code "67") (name "RES_1_OUT") (class "Default")
      (node (ref "U$9") (pin "NC-") (pinfunction "NC-_NC-") (pintype "bidirectional"))
      (node (ref "X2") (pin "P$2") (pinfunction "2_P$2") (pintype "passive"))
    )
    (net (code "68") (name "SIG1") (class "Default")
      (node (ref "IC11") (pin "10") (pinfunction "O_10") (pintype "output"))
      (node (ref "IC12") (pin "1") (pinfunction "I0_1") (pintype "input"))
    )
    (net (code "69") (name "SIG2") (class "Default")
      (node (ref "IC12") (pin "5") (pinfunction "I0_5") (pintype "input"))
      (node (ref "IC13") (pin "3") (pinfunction "O_3") (pintype "output"))
    )
    (net (code "70") (name "SIG3") (class "Default")
      (node (ref "IC12") (pin "6") (pinfunction "I1_6") (pintype "input"))
      (node (ref "IC13") (pin "4") (pinfunction "O_4") (pintype "output"))
    )
    (net (code "71") (name "SIG4") (class "Default")
      (node (ref "IC12") (pin "2") (pinfunction "I1_2") (pintype "input"))
      (node (ref "IC13") (pin "11") (pinfunction "O_11") (pintype "output"))
    )
    (net (code "72") (name "SIG5") (class "Default")
      (node (ref "IC12") (pin "10") (pinfunction "O_10") (pintype "output"))
      (node (ref "IC13") (pin "5") (pinfunction "I0_5") (pintype "input"))
    )
    (net (code "73") (name "SIG6") (class "Default")
      (node (ref "K1") (pin "3") (pinfunction "DS2_3") (pintype "passive"))
      (node (ref "R15") (pin "1") (pinfunction "1_1") (pintype "passive"))
      (node (ref "R38") (pin "2") (pinfunction "2_2") (pintype "passive"))
    )
    (net (code "74") (name "SKIDPAD") (class "Default")
      (node (ref "R12") (pin "1") (pinfunction "1_1") (pintype "passive"))
      (node (ref "R19") (pin "1") (pinfunction "1_1") (pintype "passive"))
      (node (ref "R22") (pin "2") (pinfunction "2_2") (pintype "passive"))
      (node (ref "U$14") (pin "S") (pinfunction "S_S") (pintype "bidirectional"))
    )
    (net (code "75") (name "SKIDPAD_IN") (class "Default")
      (node (ref "IC9") (pin "14") (pinfunction "Y1_14") (pintype "bidirectional"))
      (node (ref "R19") (pin "2") (pinfunction "2_2") (pintype "passive"))
      (node (ref "U$14") (pin "G") (pinfunction "G_G") (pintype "bidirectional"))
    )
    (net (code "76") (name "TEENSY_IN_BLUE") (class "Default")
      (node (ref "U$1") (pin "6") (pinfunction "-IN_6") (pintype "input"))
    )
    (net (code "77") (name "TEENSY_IN_YELLOW") (class "Default")
      (node (ref "U$1") (pin "3") (pinfunction "+IN_3") (pintype "input"))
    )
    (net (code "78") (name "TRACKDRIVE") (class "Default")
      (node (ref "R28") (pin "1") (pinfunction "1_1") (pintype "passive"))
      (node (ref "R35") (pin "2") (pinfunction "2_2") (pintype "passive"))
      (node (ref "R6") (pin "1") (pinfunction "1_1") (pintype "passive"))
      (node (ref "U$17") (pin "S") (pinfunction "S_S") (pintype "bidirectional"))
      (node (ref "X2") (pin "P$6") (pinfunction "6_P$6") (pintype "passive"))
    )
    (net (code "79") (name "TRACKDRIVE_IN") (class "Default")
      (node (ref "IC9") (pin "12") (pinfunction "Y3_12") (pintype "bidirectional"))
      (node (ref "R28") (pin "2") (pinfunction "2_2") (pintype "passive"))
      (node (ref "U$17") (pin "G") (pinfunction "G_G") (pintype "bidirectional"))
    )
    (net (code "80") (name "WATCHDOG_IN") (class "Default")
      (node (ref "IC1") (pin "7") (pinfunction "WDI_7") (pintype "bidirectional"))
    )
    (net (code "81") (name "WATCHDOG_OUT") (class "Default")
      (node (ref "IC1") (pin "5") (pinfunction "~{WDO}_5") (pintype "bidirectional"))
      (node (ref "U1") (pin "5") (pinfunction "NON-INVERTING_INPUT2_5") (pintype "input"))
    )
    (net (code "82") (name "WATCHDOG_OUT_12V") (class "Default")
      (node (ref "IC11") (pin "1") (pinfunction "I0_1") (pintype "input"))
      (node (ref "U1") (pin "7") (pinfunction "OUTPUT2_7") (pintype "output"))
    )
    (net (code "83") (name "YELLOW_LED") (class "Default")
      (node (ref "IC5") (pin "5") (pinfunction "D_1_5") (pintype "bidirectional"))
      (node (ref "IC5") (pin "6") (pinfunction "D_2_6") (pintype "bidirectional"))
      (node (ref "IC5") (pin "7") (pinfunction "D_3_7") (pintype "bidirectional"))
      (node (ref "IC5") (pin "8") (pinfunction "D_4_8") (pintype "bidirectional"))
      (node (ref "R3") (pin "2") (pinfunction "2_2") (pintype "passive"))
      (node (ref "X2") (pin "P$4") (pinfunction "4_P$4") (pintype "passive"))
    )
    (net (code "84") (name "unconnected-(BMS-CONN7-4-PadP$4)") (class "Default")
      (node (ref "BMS-CONN7") (pin "P$4") (pinfunction "4_P$4") (pintype "passive"))
    )
    (net (code "85") (name "unconnected-(IC1-RP-Pad4)") (class "Default")
      (node (ref "IC1") (pin "4") (pinfunction "RP_4") (pintype "bidirectional"))
    )
    (net (code "86") (name "unconnected-(IC1-RTH-Pad2)") (class "Default")
      (node (ref "IC1") (pin "2") (pinfunction "RTH_2") (pintype "bidirectional"))
    )
    (net (code "87") (name "unconnected-(IC1-WP-Pad6)") (class "Default")
      (node (ref "IC1") (pin "6") (pinfunction "WP_6") (pintype "bidirectional"))
    )
    (net (code "88") (name "unconnected-(IC1-~{RES}-Pad3)") (class "Default")
      (node (ref "IC1") (pin "3") (pinfunction "~{RES}_3") (pintype "bidirectional"))
    )
    (net (code "89") (name "unconnected-(IC2-Q-Pad3)") (class "Default")
      (node (ref "IC2") (pin "3") (pinfunction "Q_3") (pintype "output"))
    )
    (net (code "90") (name "unconnected-(IC9-Y7-Pad7)") (class "Default")
      (node (ref "IC9") (pin "7") (pinfunction "Y7_7") (pintype "bidirectional"))
    )
    (net (code "91") (name "unconnected-(IC10D-+IN-Pad12)") (class "Default")
      (node (ref "IC10") (pin "12") (pinfunction "+IN_12") (pintype "input"))
    )
    (net (code "92") (name "unconnected-(IC10D--IN-Pad13)") (class "Default")
      (node (ref "IC10") (pin "13") (pinfunction "-IN_13") (pintype "input"))
    )
    (net (code "93") (name "unconnected-(IC10D-OUT-Pad14)") (class "Default")
      (node (ref "IC10") (pin "14") (pinfunction "OUT_14") (pintype "output"))
    )
    (net (code "94") (name "unconnected-(IC10E-V+-Pad4)") (class "Default")
      (node (ref "IC10") (pin "4") (pinfunction "V+_4") (pintype "power_in"))
    )
  )
)
